# 16_Camera_Connector.net
KiCad netlist of a schematic drawn in Altium Designer
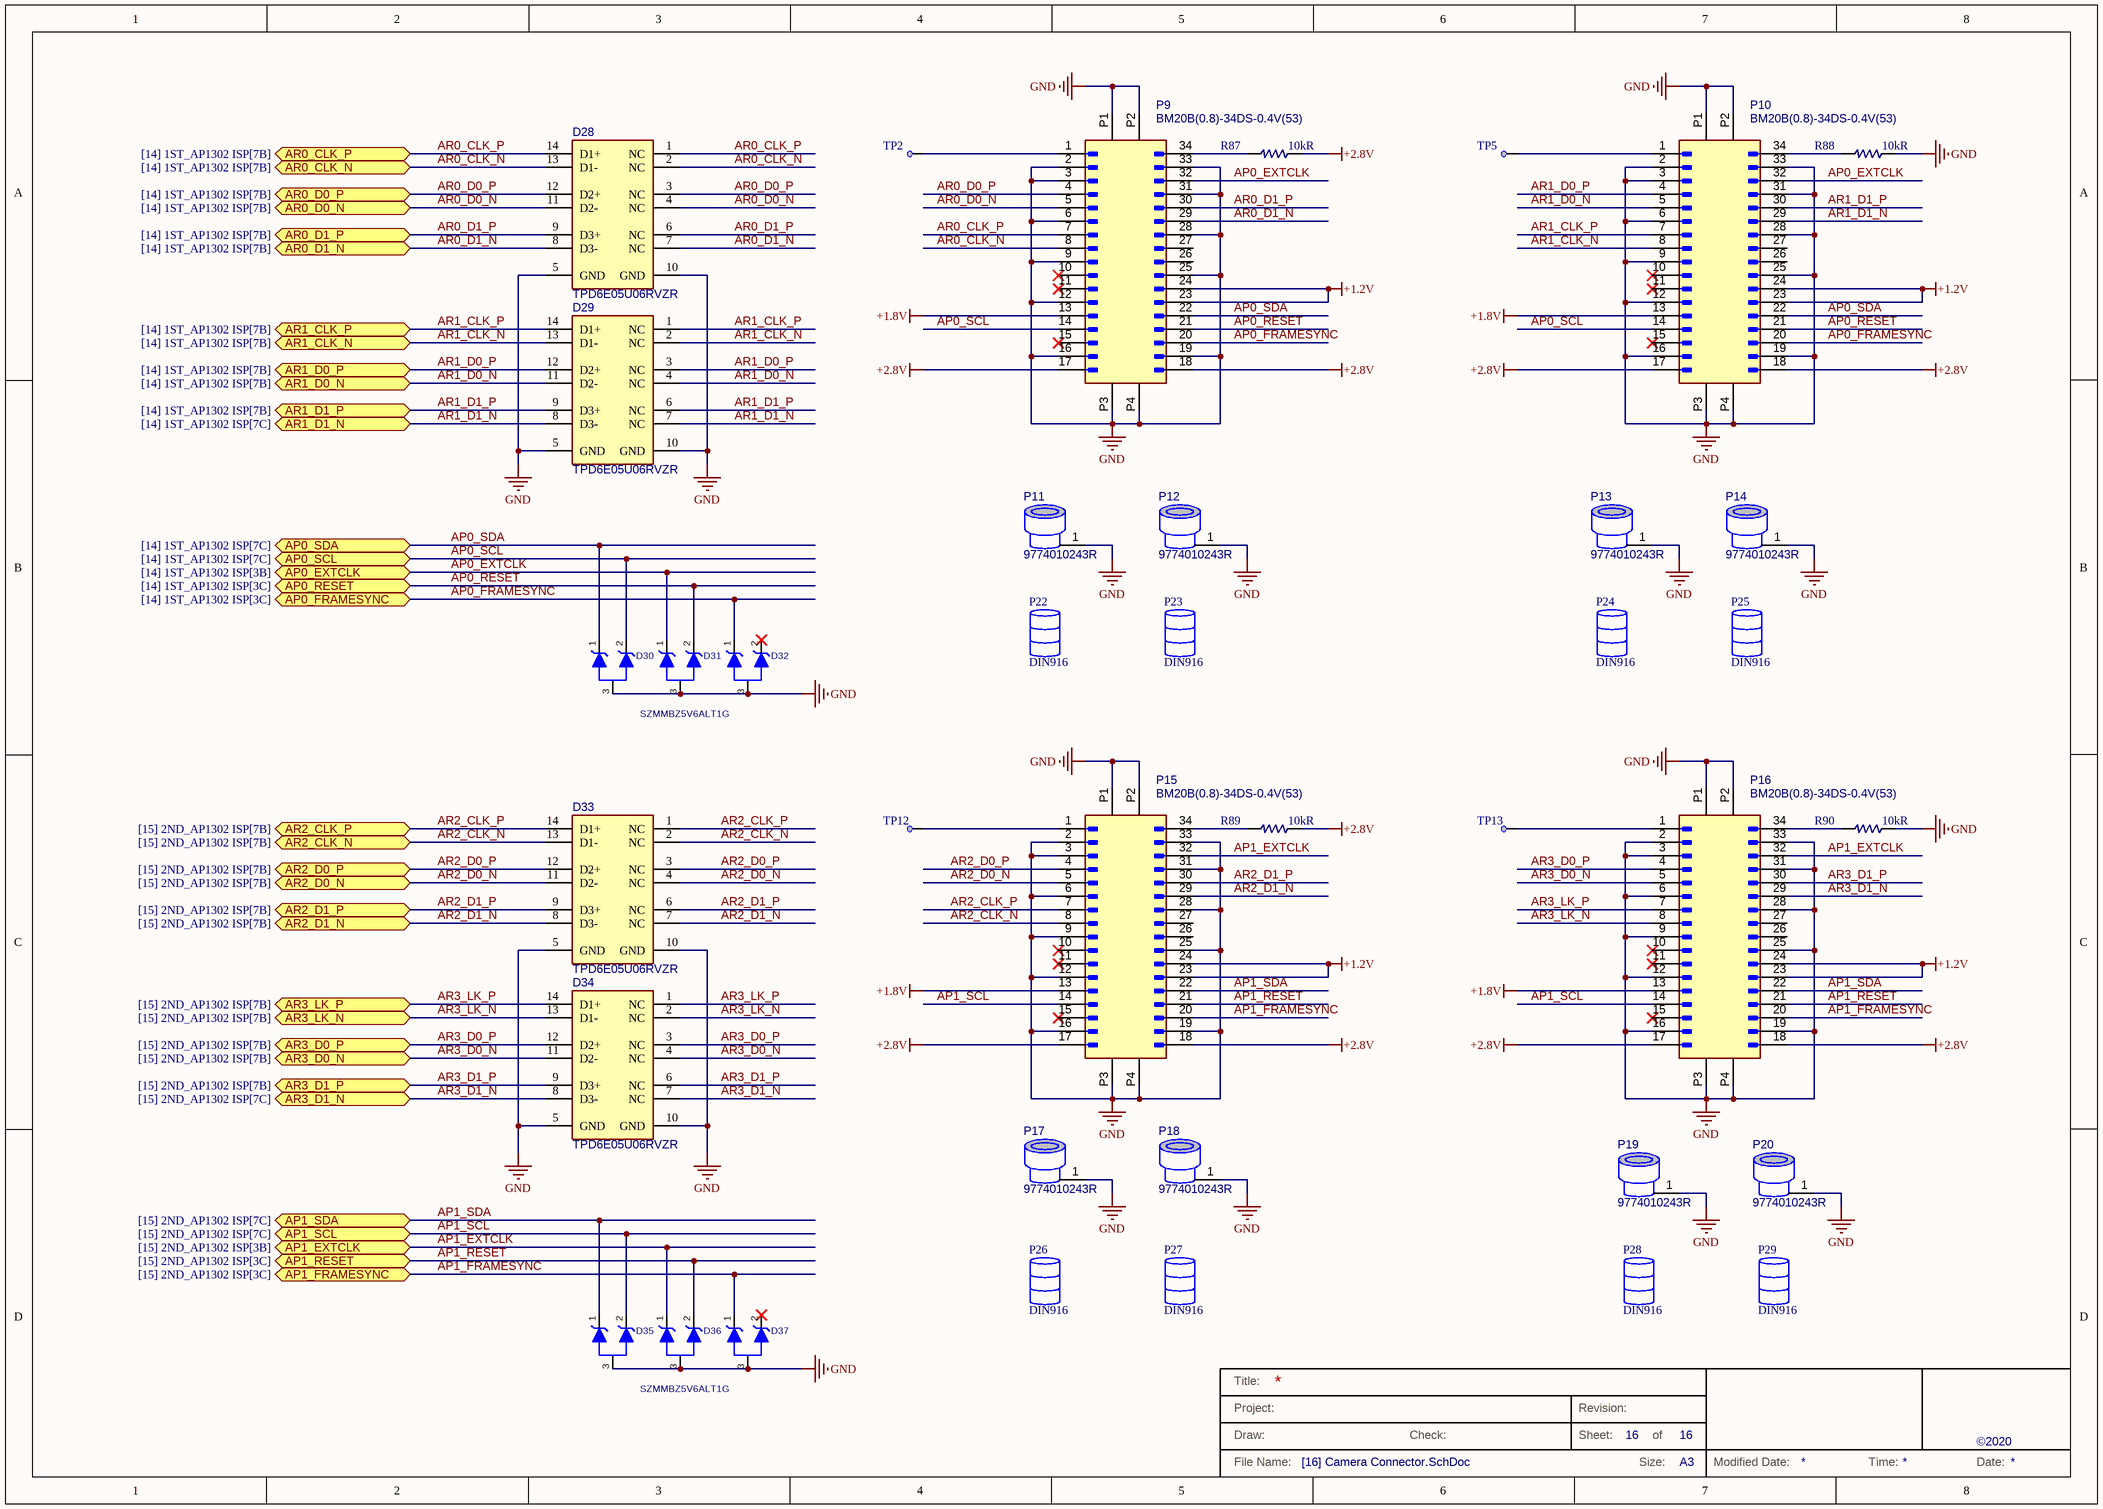
[diagram p0: [16] Camera Connector.SchDoc]

(export (version "E")
  (design (tool "Eeschema 10.0.6"))
  (components
    (comp (ref "D28")
      (value "TPD6E05U06RVZR")
      (footprint "TPD6E05U06RVZR")
      (description "ESD Suppressor Diode Array ±15kV@Air Gap/±12kV@Contact Disc 14-Pin UQFN T/R")
      (libsource (lib "3DAS_4Camera") (part "TPD6E05U06RVZR_symbol"))
    )
    (comp (ref "D29")
      (value "TPD6E05U06RVZR")
      (footprint "TPD6E05U06RVZR")
      (description "ESD Suppressor Diode Array ±15kV@Air Gap/±12kV@Contact Disc 14-Pin UQFN T/R")
      (libsource (lib "3DAS_4Camera") (part "TPD6E05U06RVZR_symbol"))
    )
    (comp (ref "D30")
      (value "SZMMBZ5V6ALT1G")
      (footprint "ONSC-SOT-23-3-318-08_V")
      (description "TVS DIODE 3V 8V SOT23-3")
      (libsource (lib "Altium Central") (part "ONSC-K1K2A3-3"))
    )
    (comp (ref "D31")
      (value "SZMMBZ5V6ALT1G")
      (footprint "ONSC-SOT-23-3-318-08_V")
      (description "TVS DIODE 3V 8V SOT23-3")
      (libsource (lib "Altium Central") (part "ONSC-K1K2A3-3"))
    )
    (comp (ref "D32")
      (value "SZMMBZ5V6ALT1G")
      (footprint "ONSC-SOT-23-3-318-08_V")
      (description "TVS DIODE 3V 8V SOT23-3")
      (libsource (lib "Altium Central") (part "ONSC-K1K2A3-3"))
    )
    (comp (ref "D33")
      (value "TPD6E05U06RVZR")
      (footprint "TPD6E05U06RVZR")
      (description "ESD Suppressor Diode Array ±15kV@Air Gap/±12kV@Contact Disc 14-Pin UQFN T/R")
      (libsource (lib "3DAS_4Camera") (part "TPD6E05U06RVZR_symbol"))
    )
    (comp (ref "D34")
      (value "TPD6E05U06RVZR")
      (footprint "TPD6E05U06RVZR")
      (description "ESD Suppressor Diode Array ±15kV@Air Gap/±12kV@Contact Disc 14-Pin UQFN T/R")
      (libsource (lib "3DAS_4Camera") (part "TPD6E05U06RVZR_symbol"))
    )
    (comp (ref "D35")
      (value "SZMMBZ5V6ALT1G")
      (footprint "ONSC-SOT-23-3-318-08_V")
      (description "TVS DIODE 3V 8V SOT23-3")
      (libsource (lib "Altium Central") (part "ONSC-K1K2A3-3"))
    )
    (comp (ref "D36")
      (value "SZMMBZ5V6ALT1G")
      (footprint "ONSC-SOT-23-3-318-08_V")
      (description "TVS DIODE 3V 8V SOT23-3")
      (libsource (lib "Altium Central") (part "ONSC-K1K2A3-3"))
    )
    (comp (ref "D37")
      (value "SZMMBZ5V6ALT1G")
      (footprint "ONSC-SOT-23-3-318-08_V")
      (description "TVS DIODE 3V 8V SOT23-3")
      (libsource (lib "Altium Central") (part "ONSC-K1K2A3-3"))
    )
    (comp (ref "P9")
      (value "BM20B(0.8)-34DS-0.4V(53)")
      (footprint "BM20B(0.8)-34DS-0.4V(51)")
      (description "Board to Board & Mezzanine Connectors 34P DR RCP B2B/B2FPC 0.8mm H 0.4mm P VSMT")
      (fields (field (name "MANUFACTURER") "Hirose"))
      (libsource (lib "3DAS_4Camera") (part "BM20B(0.8)-34DP-0.4V(51)"))
    )
    (comp (ref "P10")
      (value "BM20B(0.8)-34DS-0.4V(53)")
      (footprint "BM20B(0.8)-34DS-0.4V(51)")
      (description "Board to Board & Mezzanine Connectors 34P DR RCP B2B/B2FPC 0.8mm H 0.4mm P VSMT")
      (fields (field (name "MANUFACTURER") "Hirose"))
      (libsource (lib "3DAS_4Camera") (part "BM20B(0.8)-34DP-0.4V(51)"))
    )
    (comp (ref "P11")
      (value "9774010243R")
      (footprint "WE_9774010243R")
      (description "Spacer Material: Steel, Tin-Plated Mounting: SMT Series: WA-SMST Thread D: M2")
      (libsource (lib "3DAS_4Camera") (part "9774010243R"))
    )
    (comp (ref "P12")
      (value "9774010243R")
      (footprint "WE_9774010243R")
      (description "Spacer Material: Steel, Tin-Plated Mounting: SMT Series: WA-SMST Thread D: M2")
      (libsource (lib "3DAS_4Camera") (part "9774010243R"))
    )
    (comp (ref "P13")
      (value "9774010243R")
      (footprint "WE_9774010243R")
      (description "Spacer Material: Steel, Tin-Plated Mounting: SMT Series: WA-SMST Thread D: M2")
      (libsource (lib "3DAS_4Camera") (part "9774010243R"))
    )
    (comp (ref "P14")
      (value "9774010243R")
      (footprint "WE_9774010243R")
      (description "Spacer Material: Steel, Tin-Plated Mounting: SMT Series: WA-SMST Thread D: M2")
      (libsource (lib "3DAS_4Camera") (part "9774010243R"))
    )
    (comp (ref "P15")
      (value "BM20B(0.8)-34DS-0.4V(53)")
      (footprint "BM20B(0.8)-34DS-0.4V(51)")
      (description "Board to Board & Mezzanine Connectors 34P DR RCP B2B/B2FPC 0.8mm H 0.4mm P VSMT")
      (fields (field (name "MANUFACTURER") "Hirose"))
      (libsource (lib "3DAS_4Camera") (part "BM20B(0.8)-34DP-0.4V(51)"))
    )
    (comp (ref "P16")
      (value "BM20B(0.8)-34DS-0.4V(53)")
      (footprint "BM20B(0.8)-34DS-0.4V(51)")
      (description "Board to Board & Mezzanine Connectors 34P DR RCP B2B/B2FPC 0.8mm H 0.4mm P VSMT")
      (fields (field (name "MANUFACTURER") "Hirose"))
      (libsource (lib "3DAS_4Camera") (part "BM20B(0.8)-34DP-0.4V(51)"))
    )
    (comp (ref "P17")
      (value "9774010243R")
      (footprint "WE_9774010243R")
      (description "Spacer Material: Steel, Tin-Plated Mounting: SMT Series: WA-SMST Thread D: M2")
      (libsource (lib "3DAS_4Camera") (part "9774010243R"))
    )
    (comp (ref "P18")
      (value "9774010243R")
      (footprint "WE_9774010243R")
      (description "Spacer Material: Steel, Tin-Plated Mounting: SMT Series: WA-SMST Thread D: M2")
      (libsource (lib "3DAS_4Camera") (part "9774010243R"))
    )
    (comp (ref "P19")
      (value "9774010243R")
      (footprint "WE_9774010243R")
      (description "Spacer Material: Steel, Tin-Plated Mounting: SMT Series: WA-SMST Thread D: M2")
      (libsource (lib "3DAS_4Camera") (part "9774010243R"))
    )
    (comp (ref "P20")
      (value "9774010243R")
      (footprint "WE_9774010243R")
      (description "Spacer Material: Steel, Tin-Plated Mounting: SMT Series: WA-SMST Thread D: M2")
      (libsource (lib "3DAS_4Camera") (part "9774010243R"))
    )
    (comp (ref "P22")
      (value "DIN916")
      (footprint "DIN916")
      (description "Hexagon socket set screws with cup point")
      (libsource (lib "3DAS_4Camera") (part "DIN916"))
    )
    (comp (ref "P23")
      (value "DIN916")
      (footprint "DIN916")
      (description "Hexagon socket set screws with cup point")
      (libsource (lib "3DAS_4Camera") (part "DIN916"))
    )
    (comp (ref "P24")
      (value "DIN916")
      (footprint "DIN916")
      (description "Hexagon socket set screws with cup point")
      (libsource (lib "3DAS_4Camera") (part "DIN916"))
    )
    (comp (ref "P25")
      (value "DIN916")
      (footprint "DIN916")
      (description "Hexagon socket set screws with cup point")
      (libsource (lib "3DAS_4Camera") (part "DIN916"))
    )
    (comp (ref "P26")
      (value "DIN916")
      (footprint "DIN916")
      (description "Hexagon socket set screws with cup point")
      (libsource (lib "3DAS_4Camera") (part "DIN916"))
    )
    (comp (ref "P27")
      (value "DIN916")
      (footprint "DIN916")
      (description "Hexagon socket set screws with cup point")
      (libsource (lib "3DAS_4Camera") (part "DIN916"))
    )
    (comp (ref "P28")
      (value "DIN916")
      (footprint "DIN916")
      (description "Hexagon socket set screws with cup point")
      (libsource (lib "3DAS_4Camera") (part "DIN916"))
    )
    (comp (ref "P29")
      (value "DIN916")
      (footprint "DIN916")
      (description "Hexagon socket set screws with cup point")
      (libsource (lib "3DAS_4Camera") (part "DIN916"))
    )
    (comp (ref "R87")
      (value "10k")
      (footprint "R0402M")
      (description "RES SMD 10K OHM 1% 1/16W 0402")
      (fields
        (field (name "MANUFACTURER") "Yageo")
        (field (name "MANUFACTURER PART NUMBER") "RC0402FR-0710KL")
        (field (name "RESISTANCE") "10kR")
      )
      (libsource (lib "CommonLib") (part "RES_SMD"))
    )
    (comp (ref "R88")
      (value "10k")
      (footprint "R0402M")
      (description "RES SMD 10K OHM 1% 1/16W 0402")
      (fields
        (field (name "MANUFACTURER") "Yageo")
        (field (name "MANUFACTURER PART NUMBER") "RC0402FR-0710KL")
        (field (name "RESISTANCE") "10kR")
      )
      (libsource (lib "CommonLib") (part "RES_SMD"))
    )
    (comp (ref "R89")
      (value "10k")
      (footprint "R0402M")
      (description "RES SMD 10K OHM 1% 1/16W 0402")
      (fields
        (field (name "MANUFACTURER") "Yageo")
        (field (name "MANUFACTURER PART NUMBER") "RC0402FR-0710KL")
        (field (name "RESISTANCE") "10kR")
      )
      (libsource (lib "CommonLib") (part "RES_SMD"))
    )
    (comp (ref "R90")
      (value "10k")
      (footprint "R0402M")
      (description "RES SMD 10K OHM 1% 1/16W 0402")
      (fields
        (field (name "MANUFACTURER") "Yageo")
        (field (name "MANUFACTURER PART NUMBER") "RC0402FR-0710KL")
        (field (name "RESISTANCE") "10kR")
      )
      (libsource (lib "CommonLib") (part "RES_SMD"))
    )
    (comp (ref "TP2")
      (value "TP")
      (footprint "Test point")
      (description "TESTPOINT")
      (libsource (lib "CommonLib") (part "TestPoint"))
    )
    (comp (ref "TP5")
      (value "TP")
      (footprint "Test point")
      (description "TESTPOINT")
      (libsource (lib "CommonLib") (part "TestPoint"))
    )
    (comp (ref "TP12")
      (value "TP")
      (footprint "Test point")
      (description "TESTPOINT")
      (libsource (lib "CommonLib") (part "TestPoint"))
    )
    (comp (ref "TP13")
      (value "TP")
      (footprint "Test point")
      (description "TESTPOINT")
      (libsource (lib "CommonLib") (part "TestPoint"))
    )
  )
  (nets
    (net (code "1") (name "+1.2V") (class "Default")
      (node (ref "P10") (pin "23") (pinfunction "23_23") (pintype "passive"))
      (node (ref "P10") (pin "24") (pinfunction "24_24") (pintype "passive"))
      (node (ref "P15") (pin "23") (pinfunction "23_23") (pintype "passive"))
      (node (ref "P15") (pin "24") (pinfunction "24_24") (pintype "passive"))
      (node (ref "P16") (pin "23") (pinfunction "23_23") (pintype "passive"))
      (node (ref "P16") (pin "24") (pinfunction "24_24") (pintype "passive"))
      (node (ref "P9") (pin "23") (pinfunction "23_23") (pintype "passive"))
      (node (ref "P9") (pin "24") (pinfunction "24_24") (pintype "passive"))
    )
    (net (code "2") (name "+1.8V") (class "Default")
      (node (ref "P10") (pin "13") (pinfunction "13_13") (pintype "passive"))
      (node (ref "P15") (pin "13") (pinfunction "13_13") (pintype "passive"))
      (node (ref "P16") (pin "13") (pinfunction "13_13") (pintype "passive"))
      (node (ref "P9") (pin "13") (pinfunction "13_13") (pintype "passive"))
    )
    (net (code "3") (name "+2.8V") (class "Default")
      (node (ref "P10") (pin "17") (pinfunction "17_17") (pintype "passive"))
      (node (ref "P10") (pin "18") (pinfunction "18_18") (pintype "passive"))
      (node (ref "P15") (pin "17") (pinfunction "17_17") (pintype "passive"))
      (node (ref "P15") (pin "18") (pinfunction "18_18") (pintype "passive"))
      (node (ref "P16") (pin "17") (pinfunction "17_17") (pintype "passive"))
      (node (ref "P16") (pin "18") (pinfunction "18_18") (pintype "passive"))
      (node (ref "P9") (pin "17") (pinfunction "17_17") (pintype "passive"))
      (node (ref "P9") (pin "18") (pinfunction "18_18") (pintype "passive"))
      (node (ref "R87") (pin "2") (pinfunction "2_2") (pintype "passive"))
      (node (ref "R89") (pin "2") (pinfunction "2_2") (pintype "passive"))
    )
    (net (code "4") (name "/AP0_EXTCLK") (class "Default")
      (node (ref "D31") (pin "1") (pinfunction "K1_1") (pintype "passive"))
      (node (ref "P10") (pin "32") (pinfunction "32_32") (pintype "passive"))
      (node (ref "P9") (pin "32") (pinfunction "32_32") (pintype "passive"))
    )
    (net (code "5") (name "/AP0_FRAMESYNC") (class "Default")
      (node (ref "D32") (pin "1") (pinfunction "K1_1") (pintype "passive"))
      (node (ref "P10") (pin "20") (pinfunction "20_20") (pintype "passive"))
      (node (ref "P9") (pin "20") (pinfunction "20_20") (pintype "passive"))
    )
    (net (code "6") (name "/AP0_RESET") (class "Default")
      (node (ref "D31") (pin "2") (pinfunction "K2_2") (pintype "passive"))
      (node (ref "P10") (pin "21") (pinfunction "21_21") (pintype "passive"))
      (node (ref "P9") (pin "21") (pinfunction "21_21") (pintype "passive"))
    )
    (net (code "7") (name "/AP0_SCL") (class "Default")
      (node (ref "D30") (pin "2") (pinfunction "K2_2") (pintype "passive"))
      (node (ref "P10") (pin "14") (pinfunction "14_14") (pintype "passive"))
      (node (ref "P9") (pin "14") (pinfunction "14_14") (pintype "passive"))
    )
    (net (code "8") (name "/AP0_SDA") (class "Default")
      (node (ref "D30") (pin "1") (pinfunction "K1_1") (pintype "passive"))
      (node (ref "P10") (pin "22") (pinfunction "22_22") (pintype "passive"))
      (node (ref "P9") (pin "22") (pinfunction "22_22") (pintype "passive"))
    )
    (net (code "9") (name "/AP1_EXTCLK") (class "Default")
      (node (ref "D36") (pin "1") (pinfunction "K1_1") (pintype "passive"))
      (node (ref "P15") (pin "32") (pinfunction "32_32") (pintype "passive"))
      (node (ref "P16") (pin "32") (pinfunction "32_32") (pintype "passive"))
    )
    (net (code "10") (name "/AP1_FRAMESYNC") (class "Default")
      (node (ref "D37") (pin "1") (pinfunction "K1_1") (pintype "passive"))
      (node (ref "P15") (pin "20") (pinfunction "20_20") (pintype "passive"))
      (node (ref "P16") (pin "20") (pinfunction "20_20") (pintype "passive"))
    )
    (net (code "11") (name "/AP1_RESET") (class "Default")
      (node (ref "D36") (pin "2") (pinfunction "K2_2") (pintype "passive"))
      (node (ref "P15") (pin "21") (pinfunction "21_21") (pintype "passive"))
      (node (ref "P16") (pin "21") (pinfunction "21_21") (pintype "passive"))
    )
    (net (code "12") (name "/AP1_SCL") (class "Default")
      (node (ref "D35") (pin "2") (pinfunction "K2_2") (pintype "passive"))
      (node (ref "P15") (pin "14") (pinfunction "14_14") (pintype "passive"))
      (node (ref "P16") (pin "14") (pinfunction "14_14") (pintype "passive"))
    )
    (net (code "13") (name "/AP1_SDA") (class "Default")
      (node (ref "D35") (pin "1") (pinfunction "K1_1") (pintype "passive"))
      (node (ref "P15") (pin "22") (pinfunction "22_22") (pintype "passive"))
      (node (ref "P16") (pin "22") (pinfunction "22_22") (pintype "passive"))
    )
    (net (code "14") (name "/AR0_CLK_N") (class "Default")
      (node (ref "D28") (pin "13") (pinfunction "D1-_13") (pintype "passive"))
      (node (ref "D28") (pin "2") (pinfunction "NC_2") (pintype "passive"))
      (node (ref "P9") (pin "8") (pinfunction "8_8") (pintype "passive"))
    )
    (net (code "15") (name "/AR0_CLK_P") (class "Default")
      (node (ref "D28") (pin "1") (pinfunction "NC_1") (pintype "passive"))
      (node (ref "D28") (pin "14") (pinfunction "D1+_14") (pintype "passive"))
      (node (ref "P9") (pin "7") (pinfunction "7_7") (pintype "passive"))
    )
    (net (code "16") (name "/AR0_D0_N") (class "Default")
      (node (ref "D28") (pin "11") (pinfunction "D2-_11") (pintype "passive"))
      (node (ref "D28") (pin "4") (pinfunction "NC_4") (pintype "passive"))
      (node (ref "P9") (pin "5") (pinfunction "5_5") (pintype "passive"))
    )
    (net (code "17") (name "/AR0_D0_P") (class "Default")
      (node (ref "D28") (pin "12") (pinfunction "D2+_12") (pintype "passive"))
      (node (ref "D28") (pin "3") (pinfunction "NC_3") (pintype "passive"))
      (node (ref "P9") (pin "4") (pinfunction "4_4") (pintype "passive"))
    )
    (net (code "18") (name "/AR0_D1_N") (class "Default")
      (node (ref "D28") (pin "7") (pinfunction "NC_7") (pintype "passive"))
      (node (ref "D28") (pin "8") (pinfunction "D3-_8") (pintype "passive"))
      (node (ref "P9") (pin "29") (pinfunction "29_29") (pintype "passive"))
    )
    (net (code "19") (name "/AR0_D1_P") (class "Default")
      (node (ref "D28") (pin "6") (pinfunction "NC_6") (pintype "passive"))
      (node (ref "D28") (pin "9") (pinfunction "D3+_9") (pintype "passive"))
      (node (ref "P9") (pin "30") (pinfunction "30_30") (pintype "passive"))
    )
    (net (code "20") (name "/AR1_CLK_N") (class "Default")
      (node (ref "D29") (pin "13") (pinfunction "D1-_13") (pintype "passive"))
      (node (ref "D29") (pin "2") (pinfunction "NC_2") (pintype "passive"))
      (node (ref "P10") (pin "8") (pinfunction "8_8") (pintype "passive"))
    )
    (net (code "21") (name "/AR1_CLK_P") (class "Default")
      (node (ref "D29") (pin "1") (pinfunction "NC_1") (pintype "passive"))
      (node (ref "D29") (pin "14") (pinfunction "D1+_14") (pintype "passive"))
      (node (ref "P10") (pin "7") (pinfunction "7_7") (pintype "passive"))
    )
    (net (code "22") (name "/AR1_D0_N") (class "Default")
      (node (ref "D29") (pin "11") (pinfunction "D2-_11") (pintype "passive"))
      (node (ref "D29") (pin "4") (pinfunction "NC_4") (pintype "passive"))
      (node (ref "P10") (pin "5") (pinfunction "5_5") (pintype "passive"))
    )
    (net (code "23") (name "/AR1_D0_P") (class "Default")
      (node (ref "D29") (pin "12") (pinfunction "D2+_12") (pintype "passive"))
      (node (ref "D29") (pin "3") (pinfunction "NC_3") (pintype "passive"))
      (node (ref "P10") (pin "4") (pinfunction "4_4") (pintype "passive"))
    )
    (net (code "24") (name "/AR1_D1_N") (class "Default")
      (node (ref "D29") (pin "7") (pinfunction "NC_7") (pintype "passive"))
      (node (ref "D29") (pin "8") (pinfunction "D3-_8") (pintype "passive"))
      (node (ref "P10") (pin "29") (pinfunction "29_29") (pintype "passive"))
    )
    (net (code "25") (name "/AR1_D1_P") (class "Default")
      (node (ref "D29") (pin "6") (pinfunction "NC_6") (pintype "passive"))
      (node (ref "D29") (pin "9") (pinfunction "D3+_9") (pintype "passive"))
      (node (ref "P10") (pin "30") (pinfunction "30_30") (pintype "passive"))
    )
    (net (code "26") (name "/AR2_CLK_N") (class "Default")
      (node (ref "D33") (pin "13") (pinfunction "D1-_13") (pintype "passive"))
      (node (ref "D33") (pin "2") (pinfunction "NC_2") (pintype "passive"))
      (node (ref "P15") (pin "8") (pinfunction "8_8") (pintype "passive"))
    )
    (net (code "27") (name "/AR2_CLK_P") (class "Default")
      (node (ref "D33") (pin "1") (pinfunction "NC_1") (pintype "passive"))
      (node (ref "D33") (pin "14") (pinfunction "D1+_14") (pintype "passive"))
      (node (ref "P15") (pin "7") (pinfunction "7_7") (pintype "passive"))
    )
    (net (code "28") (name "/AR2_D0_N") (class "Default")
      (node (ref "D33") (pin "11") (pinfunction "D2-_11") (pintype "passive"))
      (node (ref "D33") (pin "4") (pinfunction "NC_4") (pintype "passive"))
      (node (ref "P15") (pin "5") (pinfunction "5_5") (pintype "passive"))
    )
    (net (code "29") (name "/AR2_D0_P") (class "Default")
      (node (ref "D33") (pin "12") (pinfunction "D2+_12") (pintype "passive"))
      (node (ref "D33") (pin "3") (pinfunction "NC_3") (pintype "passive"))
      (node (ref "P15") (pin "4") (pinfunction "4_4") (pintype "passive"))
    )
    (net (code "30") (name "/AR2_D1_N") (class "Default")
      (node (ref "D33") (pin "7") (pinfunction "NC_7") (pintype "passive"))
      (node (ref "D33") (pin "8") (pinfunction "D3-_8") (pintype "passive"))
      (node (ref "P15") (pin "29") (pinfunction "29_29") (pintype "passive"))
    )
    (net (code "31") (name "/AR2_D1_P") (class "Default")
      (node (ref "D33") (pin "6") (pinfunction "NC_6") (pintype "passive"))
      (node (ref "D33") (pin "9") (pinfunction "D3+_9") (pintype "passive"))
      (node (ref "P15") (pin "30") (pinfunction "30_30") (pintype "passive"))
    )
    (net (code "32") (name "/AR3_D0_N") (class "Default")
      (node (ref "D34") (pin "11") (pinfunction "D2-_11") (pintype "passive"))
      (node (ref "D34") (pin "4") (pinfunction "NC_4") (pintype "passive"))
      (node (ref "P16") (pin "5") (pinfunction "5_5") (pintype "passive"))
    )
    (net (code "33") (name "/AR3_D0_P") (class "Default")
      (node (ref "D34") (pin "12") (pinfunction "D2+_12") (pintype "passive"))
      (node (ref "D34") (pin "3") (pinfunction "NC_3") (pintype "passive"))
      (node (ref "P16") (pin "4") (pinfunction "4_4") (pintype "passive"))
    )
    (net (code "34") (name "/AR3_D1_N") (class "Default")
      (node (ref "D34") (pin "7") (pinfunction "NC_7") (pintype "passive"))
      (node (ref "D34") (pin "8") (pinfunction "D3-_8") (pintype "passive"))
      (node (ref "P16") (pin "29") (pinfunction "29_29") (pintype "passive"))
    )
    (net (code "35") (name "/AR3_D1_P") (class "Default")
      (node (ref "D34") (pin "6") (pinfunction "NC_6") (pintype "passive"))
      (node (ref "D34") (pin "9") (pinfunction "D3+_9") (pintype "passive"))
      (node (ref "P16") (pin "30") (pinfunction "30_30") (pintype "passive"))
    )
    (net (code "36") (name "/AR3_LK_N") (class "Default")
      (node (ref "D34") (pin "13") (pinfunction "D1-_13") (pintype "passive"))
      (node (ref "D34") (pin "2") (pinfunction "NC_2") (pintype "passive"))
      (node (ref "P16") (pin "8") (pinfunction "8_8") (pintype "passive"))
    )
    (net (code "37") (name "/AR3_LK_P") (class "Default")
      (node (ref "D34") (pin "1") (pinfunction "NC_1") (pintype "passive"))
      (node (ref "D34") (pin "14") (pinfunction "D1+_14") (pintype "passive"))
      (node (ref "P16") (pin "7") (pinfunction "7_7") (pintype "passive"))
    )
    (net (code "38") (name "GND") (class "Default")
      (node (ref "D28") (pin "10") (pinfunction "GND_10") (pintype "power_in"))
      (node (ref "D28") (pin "5") (pinfunction "GND_5") (pintype "power_in"))
      (node (ref "D29") (pin "10") (pinfunction "GND_10") (pintype "power_in"))
      (node (ref "D29") (pin "5") (pinfunction "GND_5") (pintype "power_in"))
      (node (ref "D30") (pin "3") (pinfunction "A_3") (pintype "passive"))
      (node (ref "D31") (pin "3") (pinfunction "A_3") (pintype "passive"))
      (node (ref "D32") (pin "3") (pinfunction "A_3") (pintype "passive"))
      (node (ref "D33") (pin "10") (pinfunction "GND_10") (pintype "power_in"))
      (node (ref "D33") (pin "5") (pinfunction "GND_5") (pintype "power_in"))
      (node (ref "D34") (pin "10") (pinfunction "GND_10") (pintype "power_in"))
      (node (ref "D34") (pin "5") (pinfunction "GND_5") (pintype "power_in"))
      (node (ref "D35") (pin "3") (pinfunction "A_3") (pintype "passive"))
      (node (ref "D36") (pin "3") (pinfunction "A_3") (pintype "passive"))
      (node (ref "D37") (pin "3") (pinfunction "A_3") (pintype "passive"))
      (node (ref "P10") (pin "12") (pinfunction "12_12") (pintype "passive"))
      (node (ref "P10") (pin "16") (pinfunction "16_16") (pintype "passive"))
      (node (ref "P10") (pin "19") (pinfunction "19_19") (pintype "passive"))
      (node (ref "P10") (pin "2") (pinfunction "2_2") (pintype "passive"))
      (node (ref "P10") (pin "25") (pinfunction "25_25") (pintype "passive"))
      (node (ref "P10") (pin "28") (pinfunction "28_28") (pintype "passive"))
      (node (ref "P10") (pin "3") (pinfunction "3_3") (pintype "passive"))
      (node (ref "P10") (pin "31") (pinfunction "31_31") (pintype "passive"))
      (node (ref "P10") (pin "33") (pinfunction "33_33") (pintype "passive"))
      (node (ref "P10") (pin "6") (pinfunction "6_6") (pintype "passive"))
      (node (ref "P10") (pin "9") (pinfunction "9_9") (pintype "passive"))
      (node (ref "P10") (pin "P1") (pinfunction "P1_P1") (pintype "passive"))
      (node (ref "P10") (pin "P2") (pinfunction "P2_P2") (pintype "passive"))
      (node (ref "P10") (pin "P3") (pinfunction "P3_P3") (pintype "passive"))
      (node (ref "P10") (pin "P4") (pinfunction "P4_P4") (pintype "passive"))
      (node (ref "P11") (pin "1") (pinfunction "1_1") (pintype "passive"))
      (node (ref "P12") (pin "1") (pinfunction "1_1") (pintype "passive"))
      (node (ref "P13") (pin "1") (pinfunction "1_1") (pintype "passive"))
      (node (ref "P14") (pin "1") (pinfunction "1_1") (pintype "passive"))
      (node (ref "P15") (pin "12") (pinfunction "12_12") (pintype "passive"))
      (node (ref "P15") (pin "16") (pinfunction "16_16") (pintype "passive"))
      (node (ref "P15") (pin "19") (pinfunction "19_19") (pintype "passive"))
      (node (ref "P15") (pin "2") (pinfunction "2_2") (pintype "passive"))
      (node (ref "P15") (pin "25") (pinfunction "25_25") (pintype "passive"))
      (node (ref "P15") (pin "28") (pinfunction "28_28") (pintype "passive"))
      (node (ref "P15") (pin "3") (pinfunction "3_3") (pintype "passive"))
      (node (ref "P15") (pin "31") (pinfunction "31_31") (pintype "passive"))
      (node (ref "P15") (pin "33") (pinfunction "33_33") (pintype "passive"))
      (node (ref "P15") (pin "6") (pinfunction "6_6") (pintype "passive"))
      (node (ref "P15") (pin "9") (pinfunction "9_9") (pintype "passive"))
      (node (ref "P15") (pin "P1") (pinfunction "P1_P1") (pintype "passive"))
      (node (ref "P15") (pin "P2") (pinfunction "P2_P2") (pintype "passive"))
      (node (ref "P15") (pin "P3") (pinfunction "P3_P3") (pintype "passive"))
      (node (ref "P15") (pin "P4") (pinfunction "P4_P4") (pintype "passive"))
      (node (ref "P16") (pin "12") (pinfunction "12_12") (pintype "passive"))
      (node (ref "P16") (pin "16") (pinfunction "16_16") (pintype "passive"))
      (node (ref "P16") (pin "19") (pinfunction "19_19") (pintype "passive"))
      (node (ref "P16") (pin "2") (pinfunction "2_2") (pintype "passive"))
      (node (ref "P16") (pin "25") (pinfunction "25_25") (pintype "passive"))
      (node (ref "P16") (pin "28") (pinfunction "28_28") (pintype "passive"))
      (node (ref "P16") (pin "3") (pinfunction "3_3") (pintype "passive"))
      (node (ref "P16") (pin "31") (pinfunction "31_31") (pintype "passive"))
      (node (ref "P16") (pin "33") (pinfunction "33_33") (pintype "passive"))
      (node (ref "P16") (pin "6") (pinfunction "6_6") (pintype "passive"))
      (node (ref "P16") (pin "9") (pinfunction "9_9") (pintype "passive"))
      (node (ref "P16") (pin "P1") (pinfunction "P1_P1") (pintype "passive"))
      (node (ref "P16") (pin "P2") (pinfunction "P2_P2") (pintype "passive"))
      (node (ref "P16") (pin "P3") (pinfunction "P3_P3") (pintype "passive"))
      (node (ref "P16") (pin "P4") (pinfunction "P4_P4") (pintype "passive"))
      (node (ref "P17") (pin "1") (pinfunction "1_1") (pintype "passive"))
      (node (ref "P18") (pin "1") (pinfunction "1_1") (pintype "passive"))
      (node (ref "P19") (pin "1") (pinfunction "1_1") (pintype "passive"))
      (node (ref "P20") (pin "1") (pinfunction "1_1") (pintype "passive"))
      (node (ref "P9") (pin "12") (pinfunction "12_12") (pintype "passive"))
      (node (ref "P9") (pin "16") (pinfunction "16_16") (pintype "passive"))
      (node (ref "P9") (pin "19") (pinfunction "19_19") (pintype "passive"))
      (node (ref "P9") (pin "2") (pinfunction "2_2") (pintype "passive"))
      (node (ref "P9") (pin "25") (pinfunction "25_25") (pintype "passive"))
      (node (ref "P9") (pin "28") (pinfunction "28_28") (pintype "passive"))
      (node (ref "P9") (pin "3") (pinfunction "3_3") (pintype "passive"))
      (node (ref "P9") (pin "31") (pinfunction "31_31") (pintype "passive"))
      (node (ref "P9") (pin "33") (pinfunction "33_33") (pintype "passive"))
      (node (ref "P9") (pin "6") (pinfunction "6_6") (pintype "passive"))
      (node (ref "P9") (pin "9") (pinfunction "9_9") (pintype "passive"))
      (node (ref "P9") (pin "P1") (pinfunction "P1_P1") (pintype "passive"))
      (node (ref "P9") (pin "P2") (pinfunction "P2_P2") (pintype "passive"))
      (node (ref "P9") (pin "P3") (pinfunction "P3_P3") (pintype "passive"))
      (node (ref "P9") (pin "P4") (pinfunction "P4_P4") (pintype "passive"))
      (node (ref "R88") (pin "2") (pinfunction "2_2") (pintype "passive"))
      (node (ref "R90") (pin "2") (pinfunction "2_2") (pintype "passive"))
    )
    (net (code "39") (name "Net-(P9-Pad34)") (class "Default")
      (node (ref "P9") (pin "34") (pinfunction "34_34") (pintype "passive"))
      (node (ref "R87") (pin "1") (pinfunction "1_1") (pintype "passive"))
    )
    (net (code "40") (name "Net-(P10-Pad34)") (class "Default")
      (node (ref "P10") (pin "34") (pinfunction "34_34") (pintype "passive"))
      (node (ref "R88") (pin "1") (pinfunction "1_1") (pintype "passive"))
    )
    (net (code "41") (name "Net-(P15-Pad34)") (class "Default")
      (node (ref "P15") (pin "34") (pinfunction "34_34") (pintype "passive"))
      (node (ref "R89") (pin "1") (pinfunction "1_1") (pintype "passive"))
    )
    (net (code "42") (name "Net-(P16-Pad34)") (class "Default")
      (node (ref "P16") (pin "34") (pinfunction "34_34") (pintype "passive"))
      (node (ref "R90") (pin "1") (pinfunction "1_1") (pintype "passive"))
    )
    (net (code "43") (name "Net-(TP2-TP)") (class "Default")
      (node (ref "P9") (pin "1") (pinfunction "1_1") (pintype "passive"))
      (node (ref "TP2") (pin "1") (pinfunction "TP_1") (pintype "passive"))
    )
    (net (code "44") (name "Net-(TP5-TP)") (class "Default")
      (node (ref "P10") (pin "1") (pinfunction "1_1") (pintype "passive"))
      (node (ref "TP5") (pin "1") (pinfunction "TP_1") (pintype "passive"))
    )
    (net (code "45") (name "Net-(TP12-TP)") (class "Default")
      (node (ref "P15") (pin "1") (pinfunction "1_1") (pintype "passive"))
      (node (ref "TP12") (pin "1") (pinfunction "TP_1") (pintype "passive"))
    )
    (net (code "46") (name "Net-(TP13-TP)") (class "Default")
      (node (ref "P16") (pin "1") (pinfunction "1_1") (pintype "passive"))
      (node (ref "TP13") (pin "1") (pinfunction "TP_1") (pintype "passive"))
    )
    (net (code "47") (name "unconnected-(D32-K2-Pad2)") (class "Default")
      (node (ref "D32") (pin "2") (pinfunction "K2_2") (pintype "passive+no_connect"))
    )
    (net (code "48") (name "unconnected-(D37-K2-Pad2)") (class "Default")
      (node (ref "D37") (pin "2") (pinfunction "K2_2") (pintype "passive+no_connect"))
    )
    (net (code "49") (name "unconnected-(P9-Pad10)") (class "Default")
      (node (ref "P9") (pin "10") (pinfunction "10_10") (pintype "passive+no_connect"))
    )
    (net (code "50") (name "unconnected-(P9-Pad11)") (class "Default")
      (node (ref "P9") (pin "11") (pinfunction "11_11") (pintype "passive+no_connect"))
    )
    (net (code "51") (name "unconnected-(P9-Pad15)") (class "Default")
      (node (ref "P9") (pin "15") (pinfunction "15_15") (pintype "passive+no_connect"))
    )
    (net (code "52") (name "unconnected-(P9-Pad26)") (class "Default")
      (node (ref "P9") (pin "26") (pinfunction "26_26") (pintype "passive"))
    )
    (net (code "53") (name "unconnected-(P9-Pad27)") (class "Default")
      (node (ref "P9") (pin "27") (pinfunction "27_27") (pintype "passive"))
    )
    (net (code "54") (name "unconnected-(P10-Pad10)") (class "Default")
      (node (ref "P10") (pin "10") (pinfunction "10_10") (pintype "passive+no_connect"))
    )
    (net (code "55") (name "unconnected-(P10-Pad11)") (class "Default")
      (node (ref "P10") (pin "11") (pinfunction "11_11") (pintype "passive+no_connect"))
    )
    (net (code "56") (name "unconnected-(P10-Pad15)") (class "Default")
      (node (ref "P10") (pin "15") (pinfunction "15_15") (pintype "passive+no_connect"))
    )
    (net (code "57") (name "unconnected-(P10-Pad26)") (class "Default")
      (node (ref "P10") (pin "26") (pinfunction "26_26") (pintype "passive"))
    )
    (net (code "58") (name "unconnected-(P10-Pad27)") (class "Default")
      (node (ref "P10") (pin "27") (pinfunction "27_27") (pintype "passive"))
    )
    (net (code "59") (name "unconnected-(P15-Pad10)") (class "Default")
      (node (ref "P15") (pin "10") (pinfunction "10_10") (pintype "passive+no_connect"))
    )
    (net (code "60") (name "unconnected-(P15-Pad11)") (class "Default")
      (node (ref "P15") (pin "11") (pinfunction "11_11") (pintype "passive+no_connect"))
    )
    (net (code "61") (name "unconnected-(P15-Pad15)") (class "Default")
      (node (ref "P15") (pin "15") (pinfunction "15_15") (pintype "passive+no_connect"))
    )
    (net (code "62") (name "unconnected-(P15-Pad26)") (class "Default")
      (node (ref "P15") (pin "26") (pinfunction "26_26") (pintype "passive"))
    )
    (net (code "63") (name "unconnected-(P15-Pad27)") (class "Default")
      (node (ref "P15") (pin "27") (pinfunction "27_27") (pintype "passive"))
    )
    (net (code "64") (name "unconnected-(P16-Pad10)") (class "Default")
      (node (ref "P16") (pin "10") (pinfunction "10_10") (pintype "passive+no_connect"))
    )
    (net (code "65") (name "unconnected-(P16-Pad11)") (class "Default")
      (node (ref "P16") (pin "11") (pinfunction "11_11") (pintype "passive+no_connect"))
    )
    (net (code "66") (name "unconnected-(P16-Pad15)") (class "Default")
      (node (ref "P16") (pin "15") (pinfunction "15_15") (pintype "passive+no_connect"))
    )
    (net (code "67") (name "unconnected-(P16-Pad26)") (class "Default")
      (node (ref "P16") (pin "26") (pinfunction "26_26") (pintype "passive"))
    )
    (net (code "68") (name "unconnected-(P16-Pad27)") (class "Default")
      (node (ref "P16") (pin "27") (pinfunction "27_27") (pintype "passive"))
    )
  )
)
